# analog2.net
KiCad netlist of a schematic drawn in EAGLE
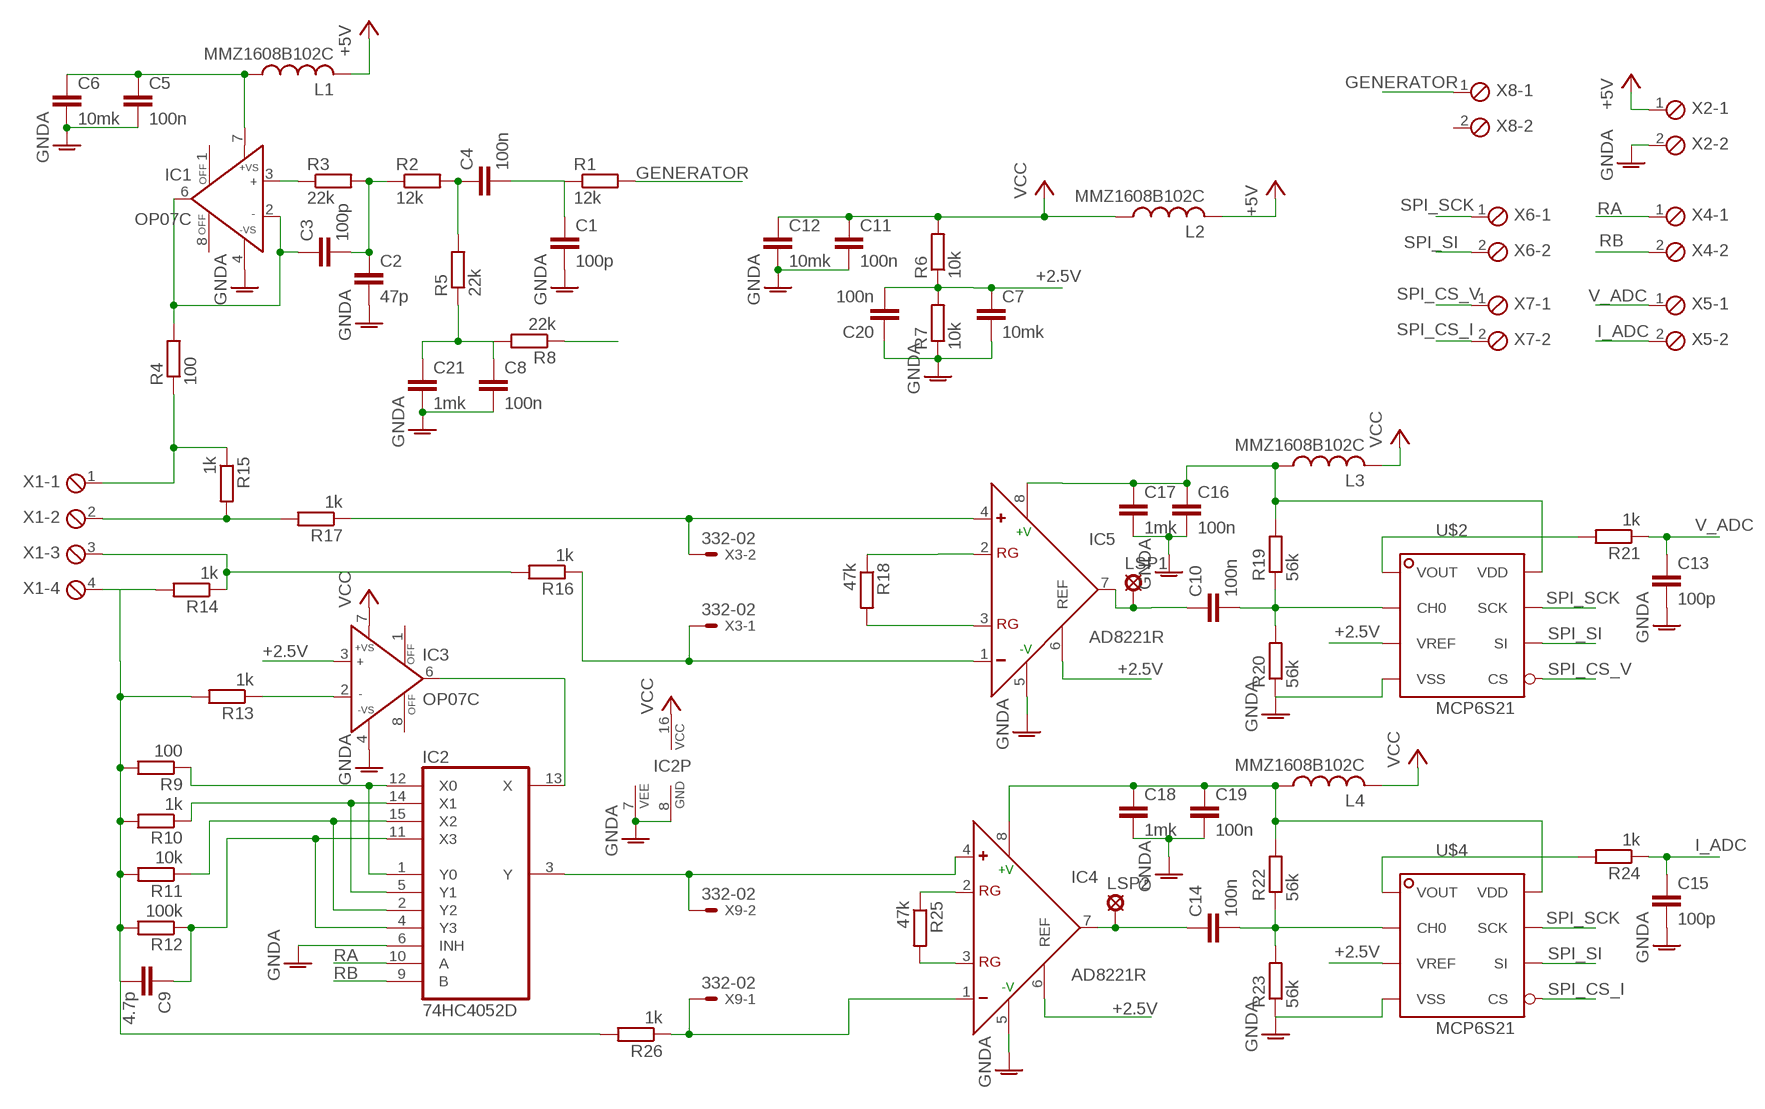
[diagram p0: schematic, sheet 1]

(export (version "E")
  (design (tool "Eeschema 10.0.6"))
  (components
    (comp (ref "C1")
      (value "100p")
      (footprint "eagle-import:C0805")
      (libsource (lib "eagle-import") (part "C-EUC0805"))
    )
    (comp (ref "C2")
      (value "47p")
      (footprint "eagle-import:C0805")
      (libsource (lib "eagle-import") (part "C-EUC0805"))
    )
    (comp (ref "C3")
      (value "100p")
      (footprint "eagle-import:C1206")
      (libsource (lib "eagle-import") (part "C-EUC1206"))
    )
    (comp (ref "C4")
      (value "100n")
      (footprint "eagle-import:C0603")
      (libsource (lib "eagle-import") (part "C-EUC0603"))
    )
    (comp (ref "C5")
      (value "100n")
      (footprint "eagle-import:C0603")
      (libsource (lib "eagle-import") (part "C-EUC0603"))
    )
    (comp (ref "C6")
      (value "10mk")
      (footprint "eagle-import:C0805")
      (libsource (lib "eagle-import") (part "C-EUC0805"))
    )
    (comp (ref "C7")
      (value "10mk")
      (footprint "eagle-import:C0805")
      (libsource (lib "eagle-import") (part "C-EUC0805"))
    )
    (comp (ref "C8")
      (value "100n")
      (footprint "eagle-import:C0603")
      (libsource (lib "eagle-import") (part "C-EUC0603"))
    )
    (comp (ref "C9")
      (value "4.7p")
      (footprint "eagle-import:C0805")
      (libsource (lib "eagle-import") (part "C-EUC0805"))
    )
    (comp (ref "C10")
      (value "100n")
      (footprint "eagle-import:C0603")
      (libsource (lib "eagle-import") (part "C-EUC0603"))
    )
    (comp (ref "C11")
      (value "100n")
      (footprint "eagle-import:C0603")
      (libsource (lib "eagle-import") (part "C-EUC0603"))
    )
    (comp (ref "C12")
      (value "10mk")
      (footprint "eagle-import:C0805")
      (libsource (lib "eagle-import") (part "C-EUC0805"))
    )
    (comp (ref "C13")
      (value "100p")
      (footprint "eagle-import:C0805")
      (libsource (lib "eagle-import") (part "C-EUC0805"))
    )
    (comp (ref "C14")
      (value "100n")
      (footprint "eagle-import:C0603")
      (libsource (lib "eagle-import") (part "C-EUC0603"))
    )
    (comp (ref "C15")
      (value "100p")
      (footprint "eagle-import:C0805")
      (libsource (lib "eagle-import") (part "C-EUC0805"))
    )
    (comp (ref "C16")
      (value "100n")
      (footprint "eagle-import:C0603")
      (libsource (lib "eagle-import") (part "C-EUC0603"))
    )
    (comp (ref "C17")
      (value "1mk")
      (footprint "eagle-import:C0603")
      (libsource (lib "eagle-import") (part "C-EUC0603"))
    )
    (comp (ref "C18")
      (value "1mk")
      (footprint "eagle-import:C0603")
      (libsource (lib "eagle-import") (part "C-EUC0603"))
    )
    (comp (ref "C19")
      (value "100n")
      (footprint "eagle-import:C0603")
      (libsource (lib "eagle-import") (part "C-EUC0603"))
    )
    (comp (ref "C20")
      (value "100n")
      (footprint "eagle-import:C0603")
      (libsource (lib "eagle-import") (part "C-EUC0603"))
    )
    (comp (ref "C21")
      (value "1mk")
      (footprint "eagle-import:C0603")
      (libsource (lib "eagle-import") (part "C-EUC0603"))
    )
    (comp (ref "IC1")
      (value "OP07C")
      (footprint "eagle-import:SO8")
      (fields (field (name "MF") "ALTERA CORPORATION") (field (name "MPN") "AD817ARZ"))
      (libsource (lib "eagle-import") (part "AD817"))
    )
    (comp (ref "IC2")
      (value "74HC4052D")
      (footprint "eagle-import:SO16")
      (libsource (lib "eagle-import") (part "4052D"))
    )
    (comp (ref "IC3")
      (value "OP07C")
      (footprint "eagle-import:SO8")
      (fields (field (name "MF") "ALTERA CORPORATION") (field (name "MPN") "AD817ARZ"))
      (libsource (lib "eagle-import") (part "AD817"))
    )
    (comp (ref "IC4")
      (value "AD8221R")
      (footprint "eagle-import:SO8")
      (fields (field (name "MPN") "AD620AR"))
      (libsource (lib "eagle-import") (part "AD8221R"))
    )
    (comp (ref "IC5")
      (value "AD8221R")
      (footprint "eagle-import:SO8")
      (fields (field (name "MPN") "AD620AR"))
      (libsource (lib "eagle-import") (part "AD8221R"))
    )
    (comp (ref "L1")
      (value "MMZ1608B102C")
      (footprint "eagle-import:R0603")
      (libsource (lib "eagle-import") (part "L-US"))
    )
    (comp (ref "L2")
      (value "MMZ1608B102C")
      (footprint "eagle-import:R0603")
      (libsource (lib "eagle-import") (part "L-US"))
    )
    (comp (ref "L3")
      (value "MMZ1608B102C")
      (footprint "eagle-import:R0603")
      (libsource (lib "eagle-import") (part "L-US"))
    )
    (comp (ref "L4")
      (value "MMZ1608B102C")
      (footprint "eagle-import:R0603")
      (libsource (lib "eagle-import") (part "L-US"))
    )
    (comp (ref "LSP1")
      (value "LSP10")
      (footprint "eagle-import:LSP10")
      (libsource (lib "eagle-import") (part "LSP10"))
    )
    (comp (ref "LSP2")
      (value "LSP10")
      (footprint "eagle-import:LSP10")
      (libsource (lib "eagle-import") (part "LSP10"))
    )
    (comp (ref "R1")
      (value "12k")
      (footprint "eagle-import:R0805")
      (libsource (lib "eagle-import") (part "R-EU_R0805"))
    )
    (comp (ref "R2")
      (value "12k")
      (footprint "eagle-import:R0805")
      (libsource (lib "eagle-import") (part "R-EU_R0805"))
    )
    (comp (ref "R3")
      (value "22k")
      (footprint "eagle-import:R0805")
      (libsource (lib "eagle-import") (part "R-EU_R0805"))
    )
    (comp (ref "R4")
      (value "100")
      (footprint "eagle-import:R0805")
      (libsource (lib "eagle-import") (part "R-EU_R0805"))
    )
    (comp (ref "R5")
      (value "22k")
      (footprint "eagle-import:R0805")
      (libsource (lib "eagle-import") (part "R-EU_R0805"))
    )
    (comp (ref "R6")
      (value "10k")
      (footprint "eagle-import:R0805")
      (libsource (lib "eagle-import") (part "R-EU_R0805"))
    )
    (comp (ref "R7")
      (value "10k")
      (footprint "eagle-import:R0805")
      (libsource (lib "eagle-import") (part "R-EU_R0805"))
    )
    (comp (ref "R8")
      (value "22k")
      (footprint "eagle-import:R0805")
      (libsource (lib "eagle-import") (part "R-EU_R0805"))
    )
    (comp (ref "R9")
      (value "100")
      (footprint "eagle-import:R0805")
      (libsource (lib "eagle-import") (part "R-EU_R0805"))
    )
    (comp (ref "R10")
      (value "1k")
      (footprint "eagle-import:R0805")
      (libsource (lib "eagle-import") (part "R-EU_R0805"))
    )
    (comp (ref "R11")
      (value "10k")
      (footprint "eagle-import:R0805")
      (libsource (lib "eagle-import") (part "R-EU_R0805"))
    )
    (comp (ref "R12")
      (value "100k")
      (footprint "eagle-import:R0805")
      (libsource (lib "eagle-import") (part "R-EU_R0805"))
    )
    (comp (ref "R13")
      (value "1k")
      (footprint "eagle-import:R0805")
      (libsource (lib "eagle-import") (part "R-EU_R0805"))
    )
    (comp (ref "R14")
      (value "1k")
      (footprint "eagle-import:R0805")
      (libsource (lib "eagle-import") (part "R-EU_R0805"))
    )
    (comp (ref "R15")
      (value "1k")
      (footprint "eagle-import:R0805")
      (libsource (lib "eagle-import") (part "R-EU_R0805"))
    )
    (comp (ref "R16")
      (value "1k")
      (footprint "eagle-import:R0805")
      (libsource (lib "eagle-import") (part "R-EU_R0805"))
    )
    (comp (ref "R17")
      (value "1k")
      (footprint "eagle-import:R0805")
      (libsource (lib "eagle-import") (part "R-EU_R0805"))
    )
    (comp (ref "R18")
      (value "47k")
      (footprint "eagle-import:R0805")
      (libsource (lib "eagle-import") (part "R-EU_R0805"))
    )
    (comp (ref "R19")
      (value "56k")
      (footprint "eagle-import:R0805")
      (libsource (lib "eagle-import") (part "R-EU_R0805"))
    )
    (comp (ref "R20")
      (value "56k")
      (footprint "eagle-import:R0805")
      (libsource (lib "eagle-import") (part "R-EU_R0805"))
    )
    (comp (ref "R21")
      (value "1k")
      (footprint "eagle-import:R0805")
      (libsource (lib "eagle-import") (part "R-EU_R0805"))
    )
    (comp (ref "R22")
      (value "56k")
      (footprint "eagle-import:R0805")
      (libsource (lib "eagle-import") (part "R-EU_R0805"))
    )
    (comp (ref "R23")
      (value "56k")
      (footprint "eagle-import:R0805")
      (libsource (lib "eagle-import") (part "R-EU_R0805"))
    )
    (comp (ref "R24")
      (value "1k")
      (footprint "eagle-import:R0805")
      (libsource (lib "eagle-import") (part "R-EU_R0805"))
    )
    (comp (ref "R25")
      (value "47k")
      (footprint "eagle-import:R0805")
      (libsource (lib "eagle-import") (part "R-EU_R0805"))
    )
    (comp (ref "R26")
      (value "1k")
      (footprint "eagle-import:R0805")
      (libsource (lib "eagle-import") (part "R-EU_R0805"))
    )
    (comp (ref "U$2")
      (value "MCP6S21")
      (footprint "eagle-import:SO8")
      (libsource (lib "eagle-import") (part "MCP6S21"))
    )
    (comp (ref "U$4")
      (value "MCP6S21")
      (footprint "eagle-import:SO8")
      (libsource (lib "eagle-import") (part "MCP6S21"))
    )
    (comp (ref "X1")
      (value "MPT4")
      (footprint "eagle-import:4POL254")
      (libsource (lib "eagle-import") (part "MPT4"))
    )
    (comp (ref "X2")
      (value "MPT2")
      (footprint "eagle-import:2POL254")
      (libsource (lib "eagle-import") (part "MPT2"))
    )
    (comp (ref "X3")
      (value "332-02")
      (footprint "eagle-import:332-02")
      (libsource (lib "eagle-import") (part "332-02"))
    )
    (comp (ref "X4")
      (value "MPT2")
      (footprint "eagle-import:2POL254")
      (libsource (lib "eagle-import") (part "MPT2"))
    )
    (comp (ref "X5")
      (value "MPT2")
      (footprint "eagle-import:2POL254")
      (libsource (lib "eagle-import") (part "MPT2"))
    )
    (comp (ref "X6")
      (value "MPT2")
      (footprint "eagle-import:2POL254")
      (libsource (lib "eagle-import") (part "MPT2"))
    )
    (comp (ref "X7")
      (value "MPT2")
      (footprint "eagle-import:2POL254")
      (libsource (lib "eagle-import") (part "MPT2"))
    )
    (comp (ref "X8")
      (value "MPT2")
      (footprint "eagle-import:2POL254")
      (libsource (lib "eagle-import") (part "MPT2"))
    )
    (comp (ref "X9")
      (value "332-02")
      (footprint "eagle-import:332-02")
      (libsource (lib "eagle-import") (part "332-02"))
    )
  )
  (nets
    (net (code "1") (name "+5V") (class "Default")
      (node (ref "L1") (pin "2") (pinfunction "2_2") (pintype "passive"))
      (node (ref "L2") (pin "2") (pinfunction "2_2") (pintype "passive"))
      (node (ref "X2") (pin "1") (pinfunction "1_1") (pintype "passive"))
    )
    (net (code "2") (name "/+2.5V") (class "Default")
      (node (ref "C20") (pin "2") (pinfunction "2_2") (pintype "passive"))
      (node (ref "C7") (pin "1") (pinfunction "1_1") (pintype "passive"))
      (node (ref "IC3") (pin "3") (pinfunction "IN+_3") (pintype "input"))
      (node (ref "IC4") (pin "6") (pinfunction "REF_6") (pintype "passive"))
      (node (ref "IC5") (pin "6") (pinfunction "REF_6") (pintype "passive"))
      (node (ref "R6") (pin "1") (pinfunction "1_1") (pintype "passive"))
      (node (ref "R7") (pin "2") (pinfunction "2_2") (pintype "passive"))
      (node (ref "R8") (pin "1") (pinfunction "1_1") (pintype "passive"))
      (node (ref "U$2") (pin "3") (pinfunction "VREF_3") (pintype "bidirectional"))
      (node (ref "U$4") (pin "3") (pinfunction "VREF_3") (pintype "bidirectional"))
    )
    (net (code "3") (name "/GENERATOR") (class "Default")
      (node (ref "R1") (pin "2") (pinfunction "2_2") (pintype "passive"))
      (node (ref "X8") (pin "1") (pinfunction "1_1") (pintype "passive"))
    )
    (net (code "4") (name "/I_ADC") (class "Default")
      (node (ref "C15") (pin "1") (pinfunction "1_1") (pintype "passive"))
      (node (ref "R24") (pin "1") (pinfunction "1_1") (pintype "passive"))
      (node (ref "X5") (pin "2") (pinfunction "1_2") (pintype "passive"))
    )
    (net (code "5") (name "/RA") (class "Default")
      (node (ref "IC2") (pin "10") (pinfunction "A_10") (pintype "input"))
      (node (ref "X4") (pin "1") (pinfunction "1_1") (pintype "passive"))
    )
    (net (code "6") (name "/RB") (class "Default")
      (node (ref "IC2") (pin "9") (pinfunction "B_9") (pintype "input"))
      (node (ref "X4") (pin "2") (pinfunction "1_2") (pintype "passive"))
    )
    (net (code "7") (name "/SPI_CS_I") (class "Default")
      (node (ref "U$4") (pin "5") (pinfunction "CS_5") (pintype "bidirectional"))
      (node (ref "X7") (pin "2") (pinfunction "1_2") (pintype "passive"))
    )
    (net (code "8") (name "/SPI_CS_V") (class "Default")
      (node (ref "U$2") (pin "5") (pinfunction "CS_5") (pintype "bidirectional"))
      (node (ref "X7") (pin "1") (pinfunction "1_1") (pintype "passive"))
    )
    (net (code "9") (name "/SPI_SCK") (class "Default")
      (node (ref "U$2") (pin "7") (pinfunction "SCK_7") (pintype "bidirectional"))
      (node (ref "U$4") (pin "7") (pinfunction "SCK_7") (pintype "bidirectional"))
      (node (ref "X6") (pin "1") (pinfunction "1_1") (pintype "passive"))
    )
    (net (code "10") (name "/SPI_SI") (class "Default")
      (node (ref "U$2") (pin "6") (pinfunction "SI_6") (pintype "bidirectional"))
      (node (ref "U$4") (pin "6") (pinfunction "SI_6") (pintype "bidirectional"))
      (node (ref "X6") (pin "2") (pinfunction "1_2") (pintype "passive"))
    )
    (net (code "11") (name "/V_ADC") (class "Default")
      (node (ref "C13") (pin "1") (pinfunction "1_1") (pintype "passive"))
      (node (ref "R21") (pin "1") (pinfunction "1_1") (pintype "passive"))
      (node (ref "X5") (pin "1") (pinfunction "1_1") (pintype "passive"))
    )
    (net (code "12") (name "GNDA") (class "Default")
      (node (ref "C1") (pin "2") (pinfunction "2_2") (pintype "passive"))
      (node (ref "C11") (pin "2") (pinfunction "2_2") (pintype "passive"))
      (node (ref "C12") (pin "2") (pinfunction "2_2") (pintype "passive"))
      (node (ref "C13") (pin "2") (pinfunction "2_2") (pintype "passive"))
      (node (ref "C15") (pin "2") (pinfunction "2_2") (pintype "passive"))
      (node (ref "C16") (pin "2") (pinfunction "2_2") (pintype "passive"))
      (node (ref "C17") (pin "2") (pinfunction "2_2") (pintype "passive"))
      (node (ref "C18") (pin "2") (pinfunction "2_2") (pintype "passive"))
      (node (ref "C19") (pin "2") (pinfunction "2_2") (pintype "passive"))
      (node (ref "C2") (pin "2") (pinfunction "2_2") (pintype "passive"))
      (node (ref "C20") (pin "1") (pinfunction "1_1") (pintype "passive"))
      (node (ref "C21") (pin "2") (pinfunction "2_2") (pintype "passive"))
      (node (ref "C5") (pin "2") (pinfunction "2_2") (pintype "passive"))
      (node (ref "C6") (pin "2") (pinfunction "2_2") (pintype "passive"))
      (node (ref "C7") (pin "2") (pinfunction "2_2") (pintype "passive"))
      (node (ref "C8") (pin "2") (pinfunction "2_2") (pintype "passive"))
      (node (ref "IC1") (pin "4") (pinfunction "-VS_4") (pintype "input"))
      (node (ref "IC2") (pin "6") (pinfunction "INH_6") (pintype "input"))
      (node (ref "IC2") (pin "7") (pinfunction "VEE_7") (pintype "power_in"))
      (node (ref "IC2") (pin "8") (pinfunction "GND_8") (pintype "power_in"))
      (node (ref "IC3") (pin "4") (pinfunction "-VS_4") (pintype "input"))
      (node (ref "IC4") (pin "5") (pinfunction "-V_5") (pintype "power_in"))
      (node (ref "IC5") (pin "5") (pinfunction "-V_5") (pintype "power_in"))
      (node (ref "R20") (pin "1") (pinfunction "1_1") (pintype "passive"))
      (node (ref "R23") (pin "1") (pinfunction "1_1") (pintype "passive"))
      (node (ref "R7") (pin "1") (pinfunction "1_1") (pintype "passive"))
      (node (ref "U$2") (pin "4") (pinfunction "VSS_4") (pintype "bidirectional"))
      (node (ref "U$4") (pin "4") (pinfunction "VSS_4") (pintype "bidirectional"))
      (node (ref "X2") (pin "2") (pinfunction "1_2") (pintype "passive"))
    )
    (net (code "13") (name "Net-(C1-Pad1)") (class "Default")
      (node (ref "C1") (pin "1") (pinfunction "1_1") (pintype "passive"))
      (node (ref "C4") (pin "2") (pinfunction "2_2") (pintype "passive"))
      (node (ref "R1") (pin "1") (pinfunction "1_1") (pintype "passive"))
    )
    (net (code "14") (name "Net-(C2-Pad1)") (class "Default")
      (node (ref "C2") (pin "1") (pinfunction "1_1") (pintype "passive"))
      (node (ref "C3") (pin "2") (pinfunction "2_2") (pintype "passive"))
      (node (ref "R2") (pin "1") (pinfunction "1_1") (pintype "passive"))
      (node (ref "R3") (pin "2") (pinfunction "2_2") (pintype "passive"))
    )
    (net (code "15") (name "Net-(C4-Pad1)") (class "Default")
      (node (ref "C4") (pin "1") (pinfunction "1_1") (pintype "passive"))
      (node (ref "R2") (pin "2") (pinfunction "2_2") (pintype "passive"))
      (node (ref "R5") (pin "2") (pinfunction "2_2") (pintype "passive"))
    )
    (net (code "16") (name "Net-(C21-Pad1)") (class "Default")
      (node (ref "C21") (pin "1") (pinfunction "1_1") (pintype "passive"))
      (node (ref "C8") (pin "1") (pinfunction "1_1") (pintype "passive"))
      (node (ref "R5") (pin "1") (pinfunction "1_1") (pintype "passive"))
      (node (ref "R8") (pin "2") (pinfunction "2_2") (pintype "passive"))
    )
    (net (code "17") (name "Net-(IC1-+VS)") (class "Default")
      (node (ref "C5") (pin "1") (pinfunction "1_1") (pintype "passive"))
      (node (ref "C6") (pin "1") (pinfunction "1_1") (pintype "passive"))
      (node (ref "IC1") (pin "7") (pinfunction "+VS_7") (pintype "input"))
      (node (ref "L1") (pin "1") (pinfunction "1_1") (pintype "passive"))
    )
    (net (code "18") (name "Net-(IC1-IN+)") (class "Default")
      (node (ref "IC1") (pin "3") (pinfunction "IN+_3") (pintype "input"))
      (node (ref "R3") (pin "1") (pinfunction "1_1") (pintype "passive"))
    )
    (net (code "19") (name "Net-(IC1-IN-)") (class "Default")
      (node (ref "C3") (pin "1") (pinfunction "1_1") (pintype "passive"))
      (node (ref "IC1") (pin "2") (pinfunction "IN-_2") (pintype "input"))
      (node (ref "IC1") (pin "6") (pinfunction "OUT_6") (pintype "output"))
      (node (ref "R4") (pin "2") (pinfunction "2_2") (pintype "passive"))
    )
    (net (code "20") (name "Net-(IC2A-X)") (class "Default")
      (node (ref "IC2") (pin "13") (pinfunction "X_13") (pintype "bidirectional"))
      (node (ref "IC3") (pin "6") (pinfunction "OUT_6") (pintype "output"))
    )
    (net (code "21") (name "Net-(IC2A-X0)") (class "Default")
      (node (ref "IC2") (pin "1") (pinfunction "Y0_1") (pintype "bidirectional"))
      (node (ref "IC2") (pin "12") (pinfunction "X0_12") (pintype "bidirectional"))
      (node (ref "R9") (pin "1") (pinfunction "1_1") (pintype "passive"))
    )
    (net (code "22") (name "Net-(IC2A-X1)") (class "Default")
      (node (ref "IC2") (pin "14") (pinfunction "X1_14") (pintype "bidirectional"))
      (node (ref "IC2") (pin "5") (pinfunction "Y1_5") (pintype "bidirectional"))
      (node (ref "R10") (pin "1") (pinfunction "1_1") (pintype "passive"))
    )
    (net (code "23") (name "Net-(IC2A-X2)") (class "Default")
      (node (ref "IC2") (pin "15") (pinfunction "X2_15") (pintype "bidirectional"))
      (node (ref "IC2") (pin "2") (pinfunction "Y2_2") (pintype "bidirectional"))
      (node (ref "R11") (pin "1") (pinfunction "1_1") (pintype "passive"))
    )
    (net (code "24") (name "Net-(IC2A-X3)") (class "Default")
      (node (ref "C9") (pin "1") (pinfunction "1_1") (pintype "passive"))
      (node (ref "IC2") (pin "11") (pinfunction "X3_11") (pintype "bidirectional"))
      (node (ref "IC2") (pin "4") (pinfunction "Y3_4") (pintype "bidirectional"))
      (node (ref "R12") (pin "1") (pinfunction "1_1") (pintype "passive"))
    )
    (net (code "25") (name "Net-(IC2A-Y)") (class "Default")
      (node (ref "IC2") (pin "3") (pinfunction "Y_3") (pintype "bidirectional"))
      (node (ref "IC4") (pin "4") (pinfunction "+_4") (pintype "input"))
      (node (ref "X9") (pin "2") (pinfunction "S_2") (pintype "passive"))
    )
    (net (code "26") (name "Net-(IC3-IN-)") (class "Default")
      (node (ref "IC3") (pin "2") (pinfunction "IN-_2") (pintype "input"))
      (node (ref "R13") (pin "1") (pinfunction "1_1") (pintype "passive"))
    )
    (net (code "27") (name "Net-(IC4-+V)") (class "Default")
      (node (ref "C18") (pin "1") (pinfunction "1_1") (pintype "passive"))
      (node (ref "C19") (pin "1") (pinfunction "1_1") (pintype "passive"))
      (node (ref "IC4") (pin "8") (pinfunction "+V_8") (pintype "power_in"))
      (node (ref "L4") (pin "1") (pinfunction "1_1") (pintype "passive"))
      (node (ref "R22") (pin "2") (pinfunction "2_2") (pintype "passive"))
      (node (ref "U$4") (pin "8") (pinfunction "VDD_8") (pintype "bidirectional"))
    )
    (net (code "28") (name "Net-(IC4--)") (class "Default")
      (node (ref "IC4") (pin "1") (pinfunction "-_1") (pintype "input"))
      (node (ref "R26") (pin "1") (pinfunction "1_1") (pintype "passive"))
      (node (ref "X9") (pin "1") (pinfunction "S_1") (pintype "passive"))
    )
    (net (code "29") (name "Net-(IC4-OUT)") (class "Default")
      (node (ref "C14") (pin "1") (pinfunction "1_1") (pintype "passive"))
      (node (ref "IC4") (pin "7") (pinfunction "OUT_7") (pintype "output"))
      (node (ref "LSP2") (pin "MP") (pinfunction "MP_MP") (pintype "passive"))
    )
    (net (code "30") (name "Net-(IC4-RG-Pad2)") (class "Default")
      (node (ref "IC4") (pin "2") (pinfunction "RG_2") (pintype "passive"))
      (node (ref "R25") (pin "1") (pinfunction "1_1") (pintype "passive"))
    )
    (net (code "31") (name "Net-(IC4-RG-Pad3)") (class "Default")
      (node (ref "IC4") (pin "3") (pinfunction "RG_3") (pintype "passive"))
      (node (ref "R25") (pin "2") (pinfunction "2_2") (pintype "passive"))
    )
    (net (code "32") (name "Net-(IC5-+)") (class "Default")
      (node (ref "IC5") (pin "4") (pinfunction "+_4") (pintype "input"))
      (node (ref "R17") (pin "1") (pinfunction "1_1") (pintype "passive"))
      (node (ref "X3") (pin "2") (pinfunction "S_2") (pintype "passive"))
    )
    (net (code "33") (name "Net-(IC5-+V)") (class "Default")
      (node (ref "C16") (pin "1") (pinfunction "1_1") (pintype "passive"))
      (node (ref "C17") (pin "1") (pinfunction "1_1") (pintype "passive"))
      (node (ref "IC5") (pin "8") (pinfunction "+V_8") (pintype "power_in"))
      (node (ref "L3") (pin "1") (pinfunction "1_1") (pintype "passive"))
      (node (ref "R19") (pin "2") (pinfunction "2_2") (pintype "passive"))
      (node (ref "U$2") (pin "8") (pinfunction "VDD_8") (pintype "bidirectional"))
    )
    (net (code "34") (name "Net-(IC5--)") (class "Default")
      (node (ref "IC5") (pin "1") (pinfunction "-_1") (pintype "input"))
      (node (ref "R16") (pin "1") (pinfunction "1_1") (pintype "passive"))
      (node (ref "X3") (pin "1") (pinfunction "S_1") (pintype "passive"))
    )
    (net (code "35") (name "Net-(IC5-OUT)") (class "Default")
      (node (ref "C10") (pin "1") (pinfunction "1_1") (pintype "passive"))
      (node (ref "IC5") (pin "7") (pinfunction "OUT_7") (pintype "output"))
      (node (ref "LSP1") (pin "MP") (pinfunction "MP_MP") (pintype "passive"))
    )
    (net (code "36") (name "Net-(IC5-RG-Pad2)") (class "Default")
      (node (ref "IC5") (pin "2") (pinfunction "RG_2") (pintype "passive"))
      (node (ref "R18") (pin "1") (pinfunction "1_1") (pintype "passive"))
    )
    (net (code "37") (name "Net-(IC5-RG-Pad3)") (class "Default")
      (node (ref "IC5") (pin "3") (pinfunction "RG_3") (pintype "passive"))
      (node (ref "R18") (pin "2") (pinfunction "2_2") (pintype "passive"))
    )
    (net (code "38") (name "Net-(R15-Pad1)") (class "Default")
      (node (ref "R15") (pin "1") (pinfunction "1_1") (pintype "passive"))
      (node (ref "R4") (pin "1") (pinfunction "1_1") (pintype "passive"))
      (node (ref "X1") (pin "1") (pinfunction "1_1") (pintype "passive"))
    )
    (net (code "39") (name "Net-(U$2-CH0)") (class "Default")
      (node (ref "C10") (pin "2") (pinfunction "2_2") (pintype "passive"))
      (node (ref "R19") (pin "1") (pinfunction "1_1") (pintype "passive"))
      (node (ref "R20") (pin "2") (pinfunction "2_2") (pintype "passive"))
      (node (ref "U$2") (pin "2") (pinfunction "CH0_2") (pintype "bidirectional"))
    )
    (net (code "40") (name "Net-(U$2-VOUT)") (class "Default")
      (node (ref "R21") (pin "2") (pinfunction "2_2") (pintype "passive"))
      (node (ref "U$2") (pin "1") (pinfunction "VOUT_1") (pintype "output"))
    )
    (net (code "41") (name "Net-(U$4-CH0)") (class "Default")
      (node (ref "C14") (pin "2") (pinfunction "2_2") (pintype "passive"))
      (node (ref "R22") (pin "1") (pinfunction "1_1") (pintype "passive"))
      (node (ref "R23") (pin "2") (pinfunction "2_2") (pintype "passive"))
      (node (ref "U$4") (pin "2") (pinfunction "CH0_2") (pintype "bidirectional"))
    )
    (net (code "42") (name "Net-(U$4-VOUT)") (class "Default")
      (node (ref "R24") (pin "2") (pinfunction "2_2") (pintype "passive"))
      (node (ref "U$4") (pin "1") (pinfunction "VOUT_1") (pintype "output"))
    )
    (net (code "43") (name "Net-(X1B-1)") (class "Default")
      (node (ref "R15") (pin "2") (pinfunction "2_2") (pintype "passive"))
      (node (ref "R17") (pin "2") (pinfunction "2_2") (pintype "passive"))
      (node (ref "X1") (pin "2") (pinfunction "1_2") (pintype "passive"))
    )
    (net (code "44") (name "Net-(X1C-1)") (class "Default")
      (node (ref "R14") (pin "1") (pinfunction "1_1") (pintype "passive"))
      (node (ref "R16") (pin "2") (pinfunction "2_2") (pintype "passive"))
      (node (ref "X1") (pin "3") (pinfunction "1_3") (pintype "passive"))
    )
    (net (code "45") (name "Net-(X1D-1)") (class "Default")
      (node (ref "C9") (pin "2") (pinfunction "2_2") (pintype "passive"))
      (node (ref "R10") (pin "2") (pinfunction "2_2") (pintype "passive"))
      (node (ref "R11") (pin "2") (pinfunction "2_2") (pintype "passive"))
      (node (ref "R12") (pin "2") (pinfunction "2_2") (pintype "passive"))
      (node (ref "R13") (pin "2") (pinfunction "2_2") (pintype "passive"))
      (node (ref "R14") (pin "2") (pinfunction "2_2") (pintype "passive"))
      (node (ref "R26") (pin "2") (pinfunction "2_2") (pintype "passive"))
      (node (ref "R9") (pin "2") (pinfunction "2_2") (pintype "passive"))
      (node (ref "X1") (pin "4") (pinfunction "1_4") (pintype "passive"))
    )
    (net (code "46") (name "VCC") (class "Default")
      (node (ref "C11") (pin "1") (pinfunction "1_1") (pintype "passive"))
      (node (ref "C12") (pin "1") (pinfunction "1_1") (pintype "passive"))
      (node (ref "IC2") (pin "16") (pinfunction "VCC_16") (pintype "power_in"))
      (node (ref "IC3") (pin "7") (pinfunction "+VS_7") (pintype "input"))
      (node (ref "L2") (pin "1") (pinfunction "1_1") (pintype "passive"))
      (node (ref "L3") (pin "2") (pinfunction "2_2") (pintype "passive"))
      (node (ref "L4") (pin "2") (pinfunction "2_2") (pintype "passive"))
      (node (ref "R6") (pin "2") (pinfunction "2_2") (pintype "passive"))
    )
    (net (code "47") (name "unconnected-(IC1-OFF-Pad1)") (class "Default")
      (node (ref "IC1") (pin "1") (pinfunction "OFF_1") (pintype "passive"))
    )
    (net (code "48") (name "unconnected-(IC1-OFF-Pad8)") (class "Default")
      (node (ref "IC1") (pin "8") (pinfunction "OFF_8") (pintype "passive"))
    )
    (net (code "49") (name "unconnected-(IC3-OFF-Pad1)") (class "Default")
      (node (ref "IC3") (pin "1") (pinfunction "OFF_1") (pintype "passive"))
    )
    (net (code "50") (name "unconnected-(IC3-OFF-Pad8)") (class "Default")
      (node (ref "IC3") (pin "8") (pinfunction "OFF_8") (pintype "passive"))
    )
    (net (code "51") (name "unconnected-(X8B-1-Pad2)") (class "Default")
      (node (ref "X8") (pin "2") (pinfunction "1_2") (pintype "passive"))
    )
  )
)
